# 6_Axis.net
KiCad netlist of a schematic drawn in Altium Designer
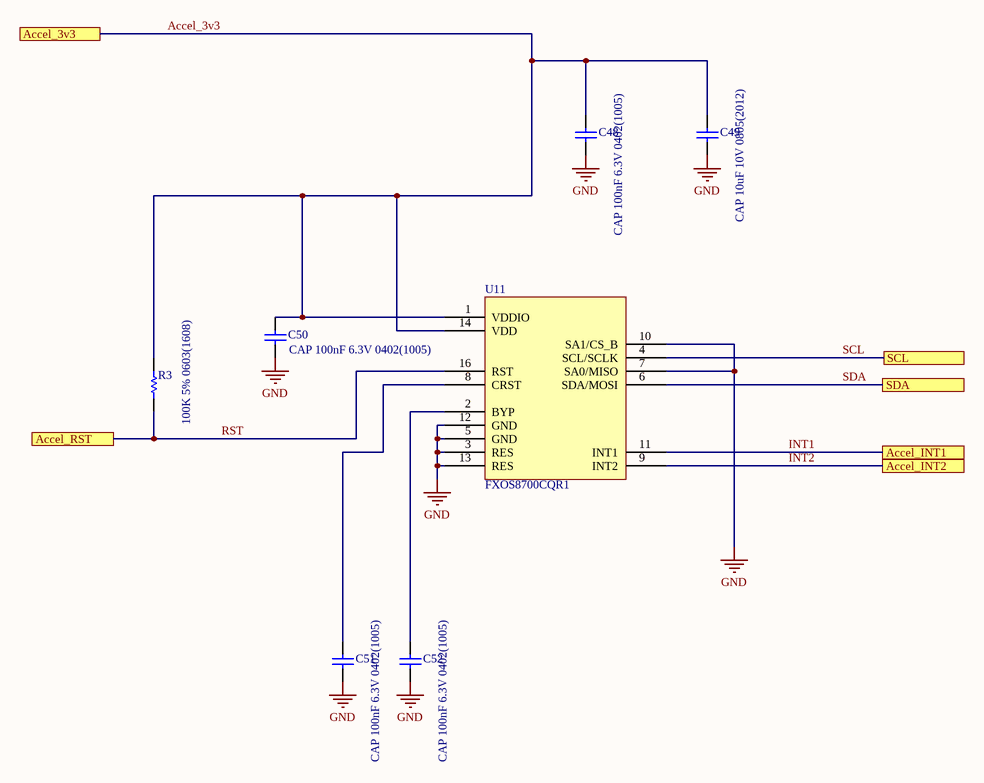
[diagram p0: 6_Axis.SchDoc]

(export (version "E")
  (design (tool "Eeschema 10.0.6"))
  (components
    (comp (ref "C48")
      (value "CAP 100nF 6.3V 0402(1005)")
      (footprint "CAPC0402(1005)60_M")
      (description "CAP 100nF 6.3V ±20% 0402 (1005 Metric) Thickness 0.6mm SMD")
      (fields (field (name "TOLERANCE") "Â±20%"))
      (libsource (lib "Altium Content Vault") (part "CAP"))
    )
    (comp (ref "C49")
      (value "CAP 10uF 10V 0805(2012)")
      (footprint "CAPC0805(2012)145_N")
      (description "CAP 10uF 10V ±20% 0805 (2012 Metric) Thickness 1.45mm SMD")
      (fields (field (name "TOLERANCE") "Â±20%"))
      (libsource (lib "Altium Content Vault") (part "CAP"))
    )
    (comp (ref "C50")
      (value "CAP 100nF 6.3V 0402(1005)")
      (footprint "CAPC0402(1005)60_M")
      (description "CAP 100nF 6.3V ±20% 0402 (1005 Metric) Thickness 0.6mm SMD")
      (fields (field (name "TOLERANCE") "Â±20%"))
      (libsource (lib "Altium Content Vault") (part "CAP"))
    )
    (comp (ref "C51")
      (value "CAP 100nF 6.3V 0402(1005)")
      (footprint "CAPC0402(1005)60_M")
      (description "CAP 100nF 6.3V ±20% 0402 (1005 Metric) Thickness 0.6mm SMD")
      (fields (field (name "TOLERANCE") "Â±20%"))
      (libsource (lib "Altium Content Vault") (part "CAP"))
    )
    (comp (ref "C52")
      (value "CAP 100nF 6.3V 0402(1005)")
      (footprint "CAPC0402(1005)60_M")
      (description "CAP 100nF 6.3V ±20% 0402 (1005 Metric) Thickness 0.6mm SMD")
      (fields (field (name "TOLERANCE") "Â±20%"))
      (libsource (lib "Altium Content Vault") (part "CAP"))
    )
    (comp (ref "R3")
      (value "100K 5% 0603(1608)")
      (footprint "RESC0603(1608)_N")
      (description "100K 0.1W 5% 0603 (1608 Metric)  SMD")
      (fields (field (name "TOLERANCE") "5 %") (field (name "POWER") "0.1 W"))
      (libsource (lib "Altium Content Vault") (part "RES"))
    )
    (comp (ref "U11")
      (value "FXOS8700CQR1")
      (footprint "QFN50P300X300X120-16N")
      (description "6-axis sensor with integrated linear accelerometer and magnetometer")
      (libsource (lib "Parts") (part "FXOS8700CQR1"))
    )
  )
  (nets
    (net (code "1") (name "/Accel_3v3") (class "Default")
      (node (ref "C48") (pin "2") (pinfunction "2_2") (pintype "passive"))
      (node (ref "C49") (pin "1") (pinfunction "1_1") (pintype "passive"))
      (node (ref "C50") (pin "2") (pinfunction "2_2") (pintype "passive"))
      (node (ref "R3") (pin "2") (pinfunction "2_2") (pintype "passive"))
      (node (ref "U11") (pin "1") (pinfunction "VDDIO_1") (pintype "passive"))
      (node (ref "U11") (pin "14") (pinfunction "VDD_14") (pintype "passive"))
    )
    (net (code "2") (name "/INT1") (class "Default")
      (node (ref "U11") (pin "11") (pinfunction "INT1_11") (pintype "passive"))
    )
    (net (code "3") (name "/INT2") (class "Default")
      (node (ref "U11") (pin "9") (pinfunction "INT2_9") (pintype "passive"))
    )
    (net (code "4") (name "/RST") (class "Default")
      (node (ref "R3") (pin "1") (pinfunction "1_1") (pintype "passive"))
      (node (ref "U11") (pin "16") (pinfunction "RST_16") (pintype "passive"))
    )
    (net (code "5") (name "/SCL") (class "Default")
      (node (ref "U11") (pin "4") (pinfunction "SCL/SCLK_4") (pintype "passive"))
    )
    (net (code "6") (name "/SDA") (class "Default")
      (node (ref "U11") (pin "6") (pinfunction "SDA/MOSI_6") (pintype "passive"))
    )
    (net (code "7") (name "GND") (class "Default")
      (node (ref "C48") (pin "1") (pinfunction "1_1") (pintype "passive"))
      (node (ref "C49") (pin "2") (pinfunction "2_2") (pintype "passive"))
      (node (ref "C50") (pin "1") (pinfunction "1_1") (pintype "passive"))
      (node (ref "C51") (pin "1") (pinfunction "1_1") (pintype "passive"))
      (node (ref "C52") (pin "1") (pinfunction "1_1") (pintype "passive"))
      (node (ref "U11") (pin "10") (pinfunction "SA1/CS_B_10") (pintype "passive"))
      (node (ref "U11") (pin "12") (pinfunction "GND_12") (pintype "passive"))
      (node (ref "U11") (pin "13") (pinfunction "RES_13") (pintype "passive"))
      (node (ref "U11") (pin "3") (pinfunction "RES_3") (pintype "passive"))
      (node (ref "U11") (pin "5") (pinfunction "GND_5") (pintype "passive"))
      (node (ref "U11") (pin "7") (pinfunction "SA0/MISO_7") (pintype "passive"))
    )
    (net (code "8") (name "Net-(U11-BYP)") (class "Default")
      (node (ref "C52") (pin "2") (pinfunction "2_2") (pintype "passive"))
      (node (ref "U11") (pin "2") (pinfunction "BYP_2") (pintype "passive"))
    )
    (net (code "9") (name "Net-(U11-CRST)") (class "Default")
      (node (ref "C51") (pin "2") (pinfunction "2_2") (pintype "passive"))
      (node (ref "U11") (pin "8") (pinfunction "CRST_8") (pintype "passive"))
    )
  )
)
